# Sewable-Connector-V1.net
KiCad netlist of a schematic drawn in EAGLE
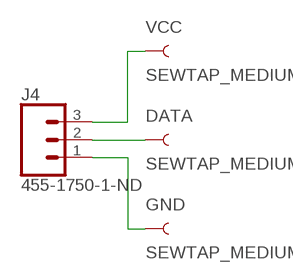
[diagram p0: schematic, sheet 1]

(export (version "E")
  (design (tool "Eeschema 10.0.6"))
  (components
    (comp (ref "DATA")
      (value "SEWTAP_MEDIUM")
      (footprint "eagle-import:PETAL-MEDIUM")
      (libsource (lib "eagle-import") (part "SEWTAP_MEDIUM"))
    )
    (comp (ref "GND")
      (value "SEWTAP_MEDIUM")
      (footprint "eagle-import:PETAL-MEDIUM")
      (libsource (lib "eagle-import") (part "SEWTAP_MEDIUM"))
    )
    (comp (ref "J4")
      (value "455-1750-1-ND")
      (footprint "eagle-import:1X03")
      (libsource (lib "eagle-import") (part "CONN_03"))
    )
    (comp (ref "VCC")
      (value "SEWTAP_MEDIUM")
      (footprint "eagle-import:PETAL-MEDIUM")
      (libsource (lib "eagle-import") (part "SEWTAP_MEDIUM"))
    )
  )
  (nets
    (net (code "1") (name "Net-(DATA-Pad1)") (class "Default")
      (node (ref "DATA") (pin "1") (pinfunction "1_1") (pintype "bidirectional"))
      (node (ref "J4") (pin "2") (pinfunction "2_2") (pintype "passive"))
    )
    (net (code "2") (name "Net-(GND-Pad1)") (class "Default")
      (node (ref "GND") (pin "1") (pinfunction "1_1") (pintype "bidirectional"))
      (node (ref "J4") (pin "1") (pinfunction "1_1") (pintype "passive"))
    )
    (net (code "3") (name "Net-(J4-Pad3)") (class "Default")
      (node (ref "J4") (pin "3") (pinfunction "3_3") (pintype "passive"))
      (node (ref "VCC") (pin "1") (pinfunction "1_1") (pintype "bidirectional"))
    )
  )
)
